# BSPD_Test_Board_rev4.net
KiCad netlist of a schematic drawn in EAGLE
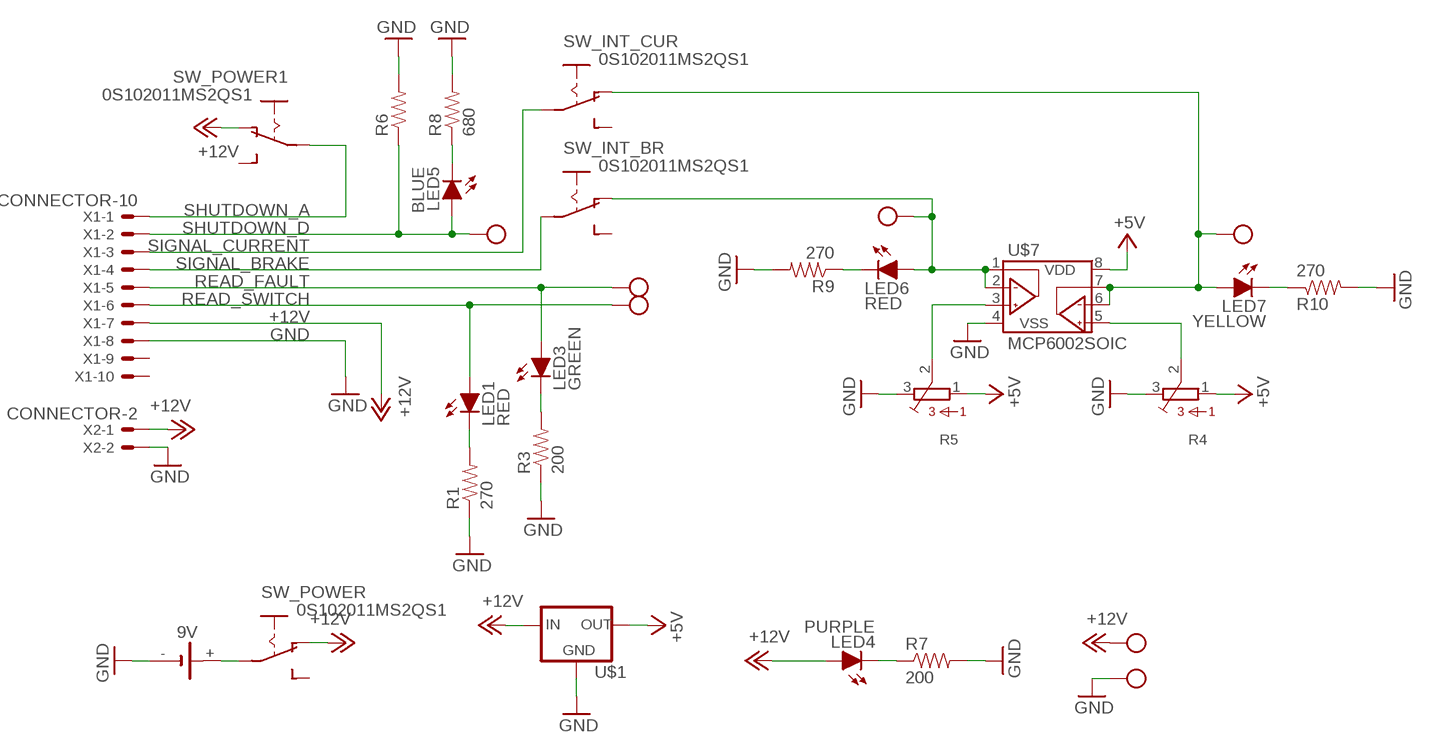
[diagram p0: schematic, sheet 1]

(export (version "E")
  (design (tool "Eeschema 10.0.6"))
  (components
    (comp (ref "9V")
      (value "1291-79")
      (footprint "eagle-import:1291-79")
      (libsource (lib "eagle-import") (part "1291-79"))
    )
    (comp (ref "LED1")
      (value "RED")
      (footprint "eagle-import:LED-5MM")
      (libsource (lib "eagle-import") (part "LED-5MM"))
    )
    (comp (ref "LED3")
      (value "GREEN")
      (footprint "eagle-import:LED-5MM")
      (libsource (lib "eagle-import") (part "LED-5MM"))
    )
    (comp (ref "LED4")
      (value "PURPLE")
      (footprint "eagle-import:LED-805")
      (libsource (lib "eagle-import") (part "LED-0805"))
    )
    (comp (ref "LED5")
      (value "BLUE")
      (footprint "eagle-import:LED-5MM")
      (libsource (lib "eagle-import") (part "LED-5MM"))
    )
    (comp (ref "LED6")
      (value "RED")
      (footprint "eagle-import:LED-805")
      (libsource (lib "eagle-import") (part "LED-0805"))
    )
    (comp (ref "LED7")
      (value "YELLOW")
      (footprint "eagle-import:LED-805")
      (libsource (lib "eagle-import") (part "LED-0805"))
    )
    (comp (ref "R1")
      (value "270")
      (footprint "eagle-import:0805")
      (libsource (lib "eagle-import") (part "RESISTOR0805-RES"))
    )
    (comp (ref "R3")
      (value "200")
      (footprint "eagle-import:0805")
      (libsource (lib "eagle-import") (part "RESISTOR0805-RES"))
    )
    (comp (ref "R4")
      (value "TRIMPOT_3296C")
      (footprint "eagle-import:TRIMPOT_3296")
      (libsource (lib "eagle-import") (part "TRIMPOT_3296C"))
    )
    (comp (ref "R5")
      (value "TRIMPOT_3296C")
      (footprint "eagle-import:TRIMPOT_3296")
      (libsource (lib "eagle-import") (part "TRIMPOT_3296C"))
    )
    (comp (ref "R6")
      (value "RESISTORPTH-1/2W")
      (footprint "eagle-import:AXIAL-0.5")
      (libsource (lib "eagle-import") (part "RESISTORPTH-1/2W"))
    )
    (comp (ref "R7")
      (value "200")
      (footprint "eagle-import:0805")
      (libsource (lib "eagle-import") (part "RESISTOR0805-RES"))
    )
    (comp (ref "R8")
      (value "680")
      (footprint "eagle-import:0805")
      (libsource (lib "eagle-import") (part "RESISTOR0805-RES"))
    )
    (comp (ref "R9")
      (value "270")
      (footprint "eagle-import:0805")
      (libsource (lib "eagle-import") (part "RESISTOR0805-RES"))
    )
    (comp (ref "R10")
      (value "270")
      (footprint "eagle-import:0805")
      (libsource (lib "eagle-import") (part "RESISTOR0805-RES"))
    )
    (comp (ref "SW_INT_BR")
      (value "0S102011MS2QS1")
      (footprint "eagle-import:0S102011MS2QS1")
      (libsource (lib "eagle-import") (part "0S102011MS2QS1"))
    )
    (comp (ref "SW_INT_CUR")
      (value "0S102011MS2QS1")
      (footprint "eagle-import:0S102011MS2QS1")
      (libsource (lib "eagle-import") (part "0S102011MS2QS1"))
    )
    (comp (ref "SW_POWER")
      (value "0S102011MS2QS1")
      (footprint "eagle-import:0S102011MS2QS1")
      (libsource (lib "eagle-import") (part "0S102011MS2QS1"))
    )
    (comp (ref "SW_POWER1")
      (value "0S102011MS2QS1")
      (footprint "eagle-import:0S102011MS2QS1")
      (libsource (lib "eagle-import") (part "0S102011MS2QS1"))
    )
    (comp (ref "U$1")
      (value "5VREG_LM340-NLM340MPX-5.0/NOPB")
      (footprint "eagle-import:SOT223")
      (libsource (lib "eagle-import") (part "5VREG_LM340-NLM340MPX-5.0/NOPB"))
    )
    (comp (ref "U$2")
      (value "TEST_POINT")
      (footprint "eagle-import:TEST_POINT")
      (libsource (lib "eagle-import") (part "TEST_POINT"))
    )
    (comp (ref "U$3")
      (value "TEST_POINT")
      (footprint "eagle-import:TEST_POINT")
      (libsource (lib "eagle-import") (part "TEST_POINT"))
    )
    (comp (ref "U$4")
      (value "TEST_POINT")
      (footprint "eagle-import:TEST_POINT")
      (libsource (lib "eagle-import") (part "TEST_POINT"))
    )
    (comp (ref "U$5")
      (value "TEST_POINT")
      (footprint "eagle-import:TEST_POINT")
      (libsource (lib "eagle-import") (part "TEST_POINT"))
    )
    (comp (ref "U$6")
      (value "TEST_POINT")
      (footprint "eagle-import:TEST_POINT")
      (libsource (lib "eagle-import") (part "TEST_POINT"))
    )
    (comp (ref "U$7")
      (value "MCP6002SOIC")
      (footprint "eagle-import:SOIC-08")
      (libsource (lib "eagle-import") (part "MCP6002SOIC"))
    )
    (comp (ref "U$8")
      (value "TEST_POINT")
      (footprint "eagle-import:TEST_POINT")
      (libsource (lib "eagle-import") (part "TEST_POINT"))
    )
    (comp (ref "U$10")
      (value "TEST_POINT")
      (footprint "eagle-import:TEST_POINT")
      (libsource (lib "eagle-import") (part "TEST_POINT"))
    )
    (comp (ref "X1")
      (value "CONNECTOR-10")
      (footprint "eagle-import:MINIFIT_5566-10")
      (libsource (lib "eagle-import") (part "CONNECTOR-10"))
    )
    (comp (ref "X2")
      (value "CONNECTOR-2")
      (footprint "eagle-import:MINIFIT_5566-2")
      (libsource (lib "eagle-import") (part "CONNECTOR-2"))
    )
  )
  (nets
    (net (code "1") (name "+5V") (class "Default")
      (node (ref "R4") (pin "1") (pinfunction "1_1") (pintype "passive"))
      (node (ref "R5") (pin "1") (pinfunction "1_1") (pintype "passive"))
      (node (ref "U$1") (pin "3") (pinfunction "OUT_3") (pintype "output"))
      (node (ref "U$7") (pin "8") (pinfunction "VDD_8") (pintype "passive"))
    )
    (net (code "2") (name "+12V") (class "Default")
      (node (ref "LED4") (pin "A") (pinfunction "A_A") (pintype "passive"))
      (node (ref "SW_POWER") (pin "P$1") (pinfunction "O_P$1") (pintype "passive"))
      (node (ref "SW_POWER1") (pin "P$1") (pinfunction "O_P$1") (pintype "passive"))
      (node (ref "U$1") (pin "1") (pinfunction "IN_1") (pintype "input"))
      (node (ref "U$5") (pin "P$1") (pinfunction "P$1_P$1") (pintype "bidirectional"))
      (node (ref "X1") (pin "7") (pinfunction "S_7") (pintype "passive"))
      (node (ref "X2") (pin "1") (pinfunction "S_1") (pintype "passive"))
    )
    (net (code "3") (name "/READ_FAULT") (class "Default")
      (node (ref "LED3") (pin "A") (pinfunction "A_A") (pintype "passive"))
      (node (ref "U$8") (pin "P$1") (pinfunction "P$1_P$1") (pintype "bidirectional"))
      (node (ref "X1") (pin "5") (pinfunction "S_5") (pintype "passive"))
    )
    (net (code "4") (name "/READ_SWITCH") (class "Default")
      (node (ref "LED1") (pin "A") (pinfunction "A_A") (pintype "passive"))
      (node (ref "U$10") (pin "P$1") (pinfunction "P$1_P$1") (pintype "bidirectional"))
      (node (ref "X1") (pin "6") (pinfunction "S_6") (pintype "passive"))
    )
    (net (code "5") (name "/SHUTDOWN_D") (class "Default")
      (node (ref "LED5") (pin "A") (pinfunction "A_A") (pintype "passive"))
      (node (ref "R6") (pin "P$1") (pinfunction "1_P$1") (pintype "passive"))
      (node (ref "U$4") (pin "P$1") (pinfunction "P$1_P$1") (pintype "bidirectional"))
      (node (ref "X1") (pin "2") (pinfunction "S_2") (pintype "passive"))
    )
    (net (code "6") (name "/SIGNAL_BRAKE") (class "Default")
      (node (ref "SW_INT_BR") (pin "P$2") (pinfunction "P_P$2") (pintype "passive"))
      (node (ref "X1") (pin "4") (pinfunction "S_4") (pintype "passive"))
    )
    (net (code "7") (name "/SIGNAL_CURRENT") (class "Default")
      (node (ref "SW_INT_CUR") (pin "P$2") (pinfunction "P_P$2") (pintype "passive"))
      (node (ref "X1") (pin "3") (pinfunction "S_3") (pintype "passive"))
    )
    (net (code "8") (name "GND") (class "Default")
      (node (ref "9V") (pin "-") (pinfunction "-_-") (pintype "passive"))
      (node (ref "R1") (pin "1") (pinfunction "1_1") (pintype "passive"))
      (node (ref "R10") (pin "2") (pinfunction "2_2") (pintype "passive"))
      (node (ref "R3") (pin "1") (pinfunction "1_1") (pintype "passive"))
      (node (ref "R4") (pin "3") (pinfunction "3_3") (pintype "passive"))
      (node (ref "R5") (pin "3") (pinfunction "3_3") (pintype "passive"))
      (node (ref "R6") (pin "P$2") (pinfunction "2_P$2") (pintype "passive"))
      (node (ref "R7") (pin "2") (pinfunction "2_2") (pintype "passive"))
      (node (ref "R8") (pin "2") (pinfunction "2_2") (pintype "passive"))
      (node (ref "R9") (pin "2") (pinfunction "2_2") (pintype "passive"))
      (node (ref "U$1") (pin "2") (pinfunction "GND_2") (pintype "input"))
      (node (ref "U$1") (pin "4") (pinfunction "GND_4") (pintype "input"))
      (node (ref "U$6") (pin "P$1") (pinfunction "P$1_P$1") (pintype "bidirectional"))
      (node (ref "U$7") (pin "4") (pinfunction "VSS_4") (pintype "passive"))
      (node (ref "X1") (pin "8") (pinfunction "S_8") (pintype "passive"))
      (node (ref "X2") (pin "2") (pinfunction "S_2") (pintype "passive"))
    )
    (net (code "9") (name "Net-(LED1-C)") (class "Default")
      (node (ref "LED1") (pin "K") (pinfunction "C_K") (pintype "passive"))
      (node (ref "R1") (pin "2") (pinfunction "2_2") (pintype "passive"))
    )
    (net (code "10") (name "Net-(LED3-C)") (class "Default")
      (node (ref "LED3") (pin "K") (pinfunction "C_K") (pintype "passive"))
      (node (ref "R3") (pin "2") (pinfunction "2_2") (pintype "passive"))
    )
    (net (code "11") (name "Net-(LED4-PadC)") (class "Default")
      (node (ref "LED4") (pin "C") (pinfunction "C_C") (pintype "passive"))
      (node (ref "R7") (pin "1") (pinfunction "1_1") (pintype "passive"))
    )
    (net (code "12") (name "Net-(LED5-C)") (class "Default")
      (node (ref "LED5") (pin "K") (pinfunction "C_K") (pintype "passive"))
      (node (ref "R8") (pin "1") (pinfunction "1_1") (pintype "passive"))
    )
    (net (code "13") (name "Net-(LED6-PadC)") (class "Default")
      (node (ref "LED6") (pin "C") (pinfunction "C_C") (pintype "passive"))
      (node (ref "R9") (pin "1") (pinfunction "1_1") (pintype "passive"))
    )
    (net (code "14") (name "Net-(LED7-PadC)") (class "Default")
      (node (ref "LED7") (pin "C") (pinfunction "C_C") (pintype "passive"))
      (node (ref "R10") (pin "1") (pinfunction "1_1") (pintype "passive"))
    )
    (net (code "15") (name "Net-(SW_INT_BR-O)") (class "Default")
      (node (ref "LED6") (pin "A") (pinfunction "A_A") (pintype "passive"))
      (node (ref "SW_INT_BR") (pin "P$1") (pinfunction "O_P$1") (pintype "passive"))
      (node (ref "U$3") (pin "P$1") (pinfunction "P$1_P$1") (pintype "bidirectional"))
      (node (ref "U$7") (pin "1") (pinfunction "VOUTA_1") (pintype "passive"))
      (node (ref "U$7") (pin "2") (pinfunction "VINA-_2") (pintype "passive"))
    )
    (net (code "16") (name "Net-(SW_INT_CUR-O)") (class "Default")
      (node (ref "LED7") (pin "A") (pinfunction "A_A") (pintype "passive"))
      (node (ref "SW_INT_CUR") (pin "P$1") (pinfunction "O_P$1") (pintype "passive"))
      (node (ref "U$2") (pin "P$1") (pinfunction "P$1_P$1") (pintype "bidirectional"))
      (node (ref "U$7") (pin "6") (pinfunction "VINB-_6") (pintype "passive"))
      (node (ref "U$7") (pin "7") (pinfunction "VOUTB_7") (pintype "passive"))
    )
    (net (code "17") (name "Net-(SW_POWER-P)") (class "Default")
      (node (ref "9V") (pin "+") (pinfunction "+_+") (pintype "passive"))
      (node (ref "SW_POWER") (pin "P$2") (pinfunction "P_P$2") (pintype "passive"))
    )
    (net (code "18") (name "Net-(SW_POWER1-P)") (class "Default")
      (node (ref "SW_POWER1") (pin "P$2") (pinfunction "P_P$2") (pintype "passive"))
      (node (ref "X1") (pin "1") (pinfunction "S_1") (pintype "passive"))
    )
    (net (code "19") (name "Net-(U$7-VINA+)") (class "Default")
      (node (ref "R5") (pin "2") (pinfunction "2_2") (pintype "passive"))
      (node (ref "U$7") (pin "3") (pinfunction "VINA+_3") (pintype "passive"))
    )
    (net (code "20") (name "Net-(U$7-VINB+)") (class "Default")
      (node (ref "R4") (pin "2") (pinfunction "2_2") (pintype "passive"))
      (node (ref "U$7") (pin "5") (pinfunction "VINB+_5") (pintype "passive"))
    )
    (net (code "21") (name "unconnected-(SW_INT_BR-S-PadP$3)") (class "Default")
      (node (ref "SW_INT_BR") (pin "P$3") (pinfunction "S_P$3") (pintype "passive"))
    )
    (net (code "22") (name "unconnected-(SW_INT_CUR-S-PadP$3)") (class "Default")
      (node (ref "SW_INT_CUR") (pin "P$3") (pinfunction "S_P$3") (pintype "passive"))
    )
    (net (code "23") (name "unconnected-(SW_POWER-S-PadP$3)") (class "Default")
      (node (ref "SW_POWER") (pin "P$3") (pinfunction "S_P$3") (pintype "passive"))
    )
    (net (code "24") (name "unconnected-(SW_POWER1-S-PadP$3)") (class "Default")
      (node (ref "SW_POWER1") (pin "P$3") (pinfunction "S_P$3") (pintype "passive"))
    )
    (net (code "25") (name "unconnected-(X1B-S-Pad10)") (class "Default")
      (node (ref "X1") (pin "10") (pinfunction "S_10") (pintype "passive"))
    )
    (net (code "26") (name "unconnected-(X1J-S-Pad9)") (class "Default")
      (node (ref "X1") (pin "9") (pinfunction "S_9") (pintype "passive"))
    )
  )
)
